# untitled1sch.net
KiCad netlist of a schematic drawn in EAGLE
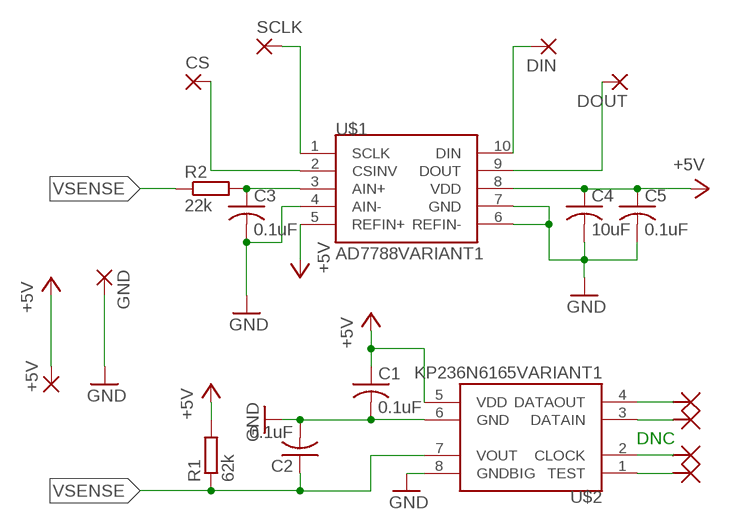
[diagram p0: schematic, sheet 1]

(export (version "E")
  (design (tool "Eeschema 10.0.6"))
  (components
    (comp (ref "+5V")
      (value "WIREPAD1,6/0,8")
      (footprint "eagle-import:1,6_0,8")
      (libsource (lib "eagle-import") (part "WIREPAD1,6/0,8"))
    )
    (comp (ref "C1")
      (value "0.1uF")
      (footprint "eagle-import:C0805")
      (libsource (lib "eagle-import") (part "C-USC0805"))
    )
    (comp (ref "C2")
      (value "0.1uF")
      (footprint "eagle-import:C0805")
      (libsource (lib "eagle-import") (part "C-USC0805"))
    )
    (comp (ref "C3")
      (value "0.1uF")
      (footprint "eagle-import:C0805")
      (libsource (lib "eagle-import") (part "C-USC0805"))
    )
    (comp (ref "C4")
      (value "10uF")
      (footprint "eagle-import:C0805")
      (libsource (lib "eagle-import") (part "C-USC0805"))
    )
    (comp (ref "C5")
      (value "0.1uF")
      (footprint "eagle-import:C0805")
      (libsource (lib "eagle-import") (part "C-USC0805"))
    )
    (comp (ref "CS")
      (value "WIREPAD1,6/0,8")
      (footprint "eagle-import:1,6_0,8")
      (libsource (lib "eagle-import") (part "WIREPAD1,6/0,8"))
    )
    (comp (ref "DIN")
      (value "WIREPAD1,6/0,8")
      (footprint "eagle-import:1,6_0,8")
      (libsource (lib "eagle-import") (part "WIREPAD1,6/0,8"))
    )
    (comp (ref "DOUT")
      (value "WIREPAD1,6/0,8")
      (footprint "eagle-import:1,6_0,8")
      (libsource (lib "eagle-import") (part "WIREPAD1,6/0,8"))
    )
    (comp (ref "GND")
      (value "WIREPAD1,6/0,8")
      (footprint "eagle-import:1,6_0,8")
      (libsource (lib "eagle-import") (part "WIREPAD1,6/0,8"))
    )
    (comp (ref "R1")
      (value "62k")
      (footprint "eagle-import:R0603")
      (libsource (lib "eagle-import") (part "R-EU_R0603"))
    )
    (comp (ref "R2")
      (value "22k")
      (footprint "eagle-import:R0603")
      (libsource (lib "eagle-import") (part "R-EU_R0603"))
    )
    (comp (ref "SCLK")
      (value "WIREPAD1,6/0,8")
      (footprint "eagle-import:1,6_0,8")
      (libsource (lib "eagle-import") (part "WIREPAD1,6/0,8"))
    )
    (comp (ref "U$1")
      (value "AD7788VARIANT1")
      (footprint "eagle-import:AD7788")
      (libsource (lib "eagle-import") (part "AD7788VARIANT1"))
    )
    (comp (ref "U$2")
      (value "KP236N6165VARIANT1")
      (footprint "eagle-import:KP236N6165")
      (libsource (lib "eagle-import") (part "KP236N6165VARIANT1"))
    )
  )
  (nets
    (net (code "1") (name "+5V") (class "Default")
      (node (ref "+5V") (pin "1") (pinfunction "P_1") (pintype "passive"))
      (node (ref "C1") (pin "1") (pinfunction "1_1") (pintype "passive"))
      (node (ref "C4") (pin "1") (pinfunction "1_1") (pintype "passive"))
      (node (ref "C5") (pin "1") (pinfunction "1_1") (pintype "passive"))
      (node (ref "R1") (pin "2") (pinfunction "2_2") (pintype "passive"))
      (node (ref "U$1") (pin "5") (pinfunction "REFIN+_5") (pintype "bidirectional"))
      (node (ref "U$1") (pin "8") (pinfunction "VDD_8") (pintype "bidirectional"))
      (node (ref "U$2") (pin "5") (pinfunction "VDD_5") (pintype "bidirectional"))
    )
    (net (code "2") (name "GND") (class "Default")
      (node (ref "C1") (pin "2") (pinfunction "2_2") (pintype "passive"))
      (node (ref "C2") (pin "2") (pinfunction "2_2") (pintype "passive"))
      (node (ref "C3") (pin "2") (pinfunction "2_2") (pintype "passive"))
      (node (ref "C4") (pin "2") (pinfunction "2_2") (pintype "passive"))
      (node (ref "C5") (pin "2") (pinfunction "2_2") (pintype "passive"))
      (node (ref "GND") (pin "1") (pinfunction "P_1") (pintype "passive"))
      (node (ref "U$1") (pin "4") (pinfunction "AIN-_4") (pintype "bidirectional"))
      (node (ref "U$1") (pin "6") (pinfunction "REFIN-_6") (pintype "bidirectional"))
      (node (ref "U$1") (pin "7") (pinfunction "GND_7") (pintype "bidirectional"))
      (node (ref "U$2") (pin "6") (pinfunction "GND_6") (pintype "bidirectional"))
      (node (ref "U$2") (pin "8") (pinfunction "GNDBIG_8") (pintype "bidirectional"))
    )
    (net (code "3") (name "Net-(CS-P)") (class "Default")
      (node (ref "CS") (pin "1") (pinfunction "P_1") (pintype "passive"))
      (node (ref "U$1") (pin "2") (pinfunction "CSINV_2") (pintype "bidirectional"))
    )
    (net (code "4") (name "Net-(DIN-P)") (class "Default")
      (node (ref "DIN") (pin "1") (pinfunction "P_1") (pintype "passive"))
      (node (ref "U$1") (pin "10") (pinfunction "DIN_10") (pintype "bidirectional"))
    )
    (net (code "5") (name "Net-(DOUT-P)") (class "Default")
      (node (ref "DOUT") (pin "1") (pinfunction "P_1") (pintype "passive"))
      (node (ref "U$1") (pin "9") (pinfunction "DOUT_9") (pintype "bidirectional"))
    )
    (net (code "6") (name "Net-(SCLK-P)") (class "Default")
      (node (ref "SCLK") (pin "1") (pinfunction "P_1") (pintype "passive"))
      (node (ref "U$1") (pin "1") (pinfunction "SCLK_1") (pintype "bidirectional"))
    )
    (net (code "7") (name "Net-(U$1-AIN+)") (class "Default")
      (node (ref "C3") (pin "1") (pinfunction "1_1") (pintype "passive"))
      (node (ref "R2") (pin "2") (pinfunction "2_2") (pintype "passive"))
      (node (ref "U$1") (pin "3") (pinfunction "AIN+_3") (pintype "bidirectional"))
    )
    (net (code "8") (name "VSENSE") (class "Default")
      (node (ref "C2") (pin "1") (pinfunction "1_1") (pintype "passive"))
      (node (ref "R1") (pin "1") (pinfunction "1_1") (pintype "passive"))
      (node (ref "R2") (pin "1") (pinfunction "1_1") (pintype "passive"))
      (node (ref "U$2") (pin "7") (pinfunction "VOUT_7") (pintype "bidirectional"))
    )
    (net (code "9") (name "unconnected-(U$2-CLOCK-Pad2)") (class "Default")
      (node (ref "U$2") (pin "2") (pinfunction "CLOCK_2") (pintype "bidirectional"))
    )
    (net (code "10") (name "unconnected-(U$2-DATAIN-Pad3)") (class "Default")
      (node (ref "U$2") (pin "3") (pinfunction "DATAIN_3") (pintype "bidirectional"))
    )
    (net (code "11") (name "unconnected-(U$2-DATAOUT-Pad4)") (class "Default")
      (node (ref "U$2") (pin "4") (pinfunction "DATAOUT_4") (pintype "bidirectional"))
    )
    (net (code "12") (name "unconnected-(U$2-TEST-Pad1)") (class "Default")
      (node (ref "U$2") (pin "1") (pinfunction "TEST_1") (pintype "bidirectional"))
    )
  )
)
